# SOM_BOOT.net
KiCad netlist of a schematic drawn in Altium Designer
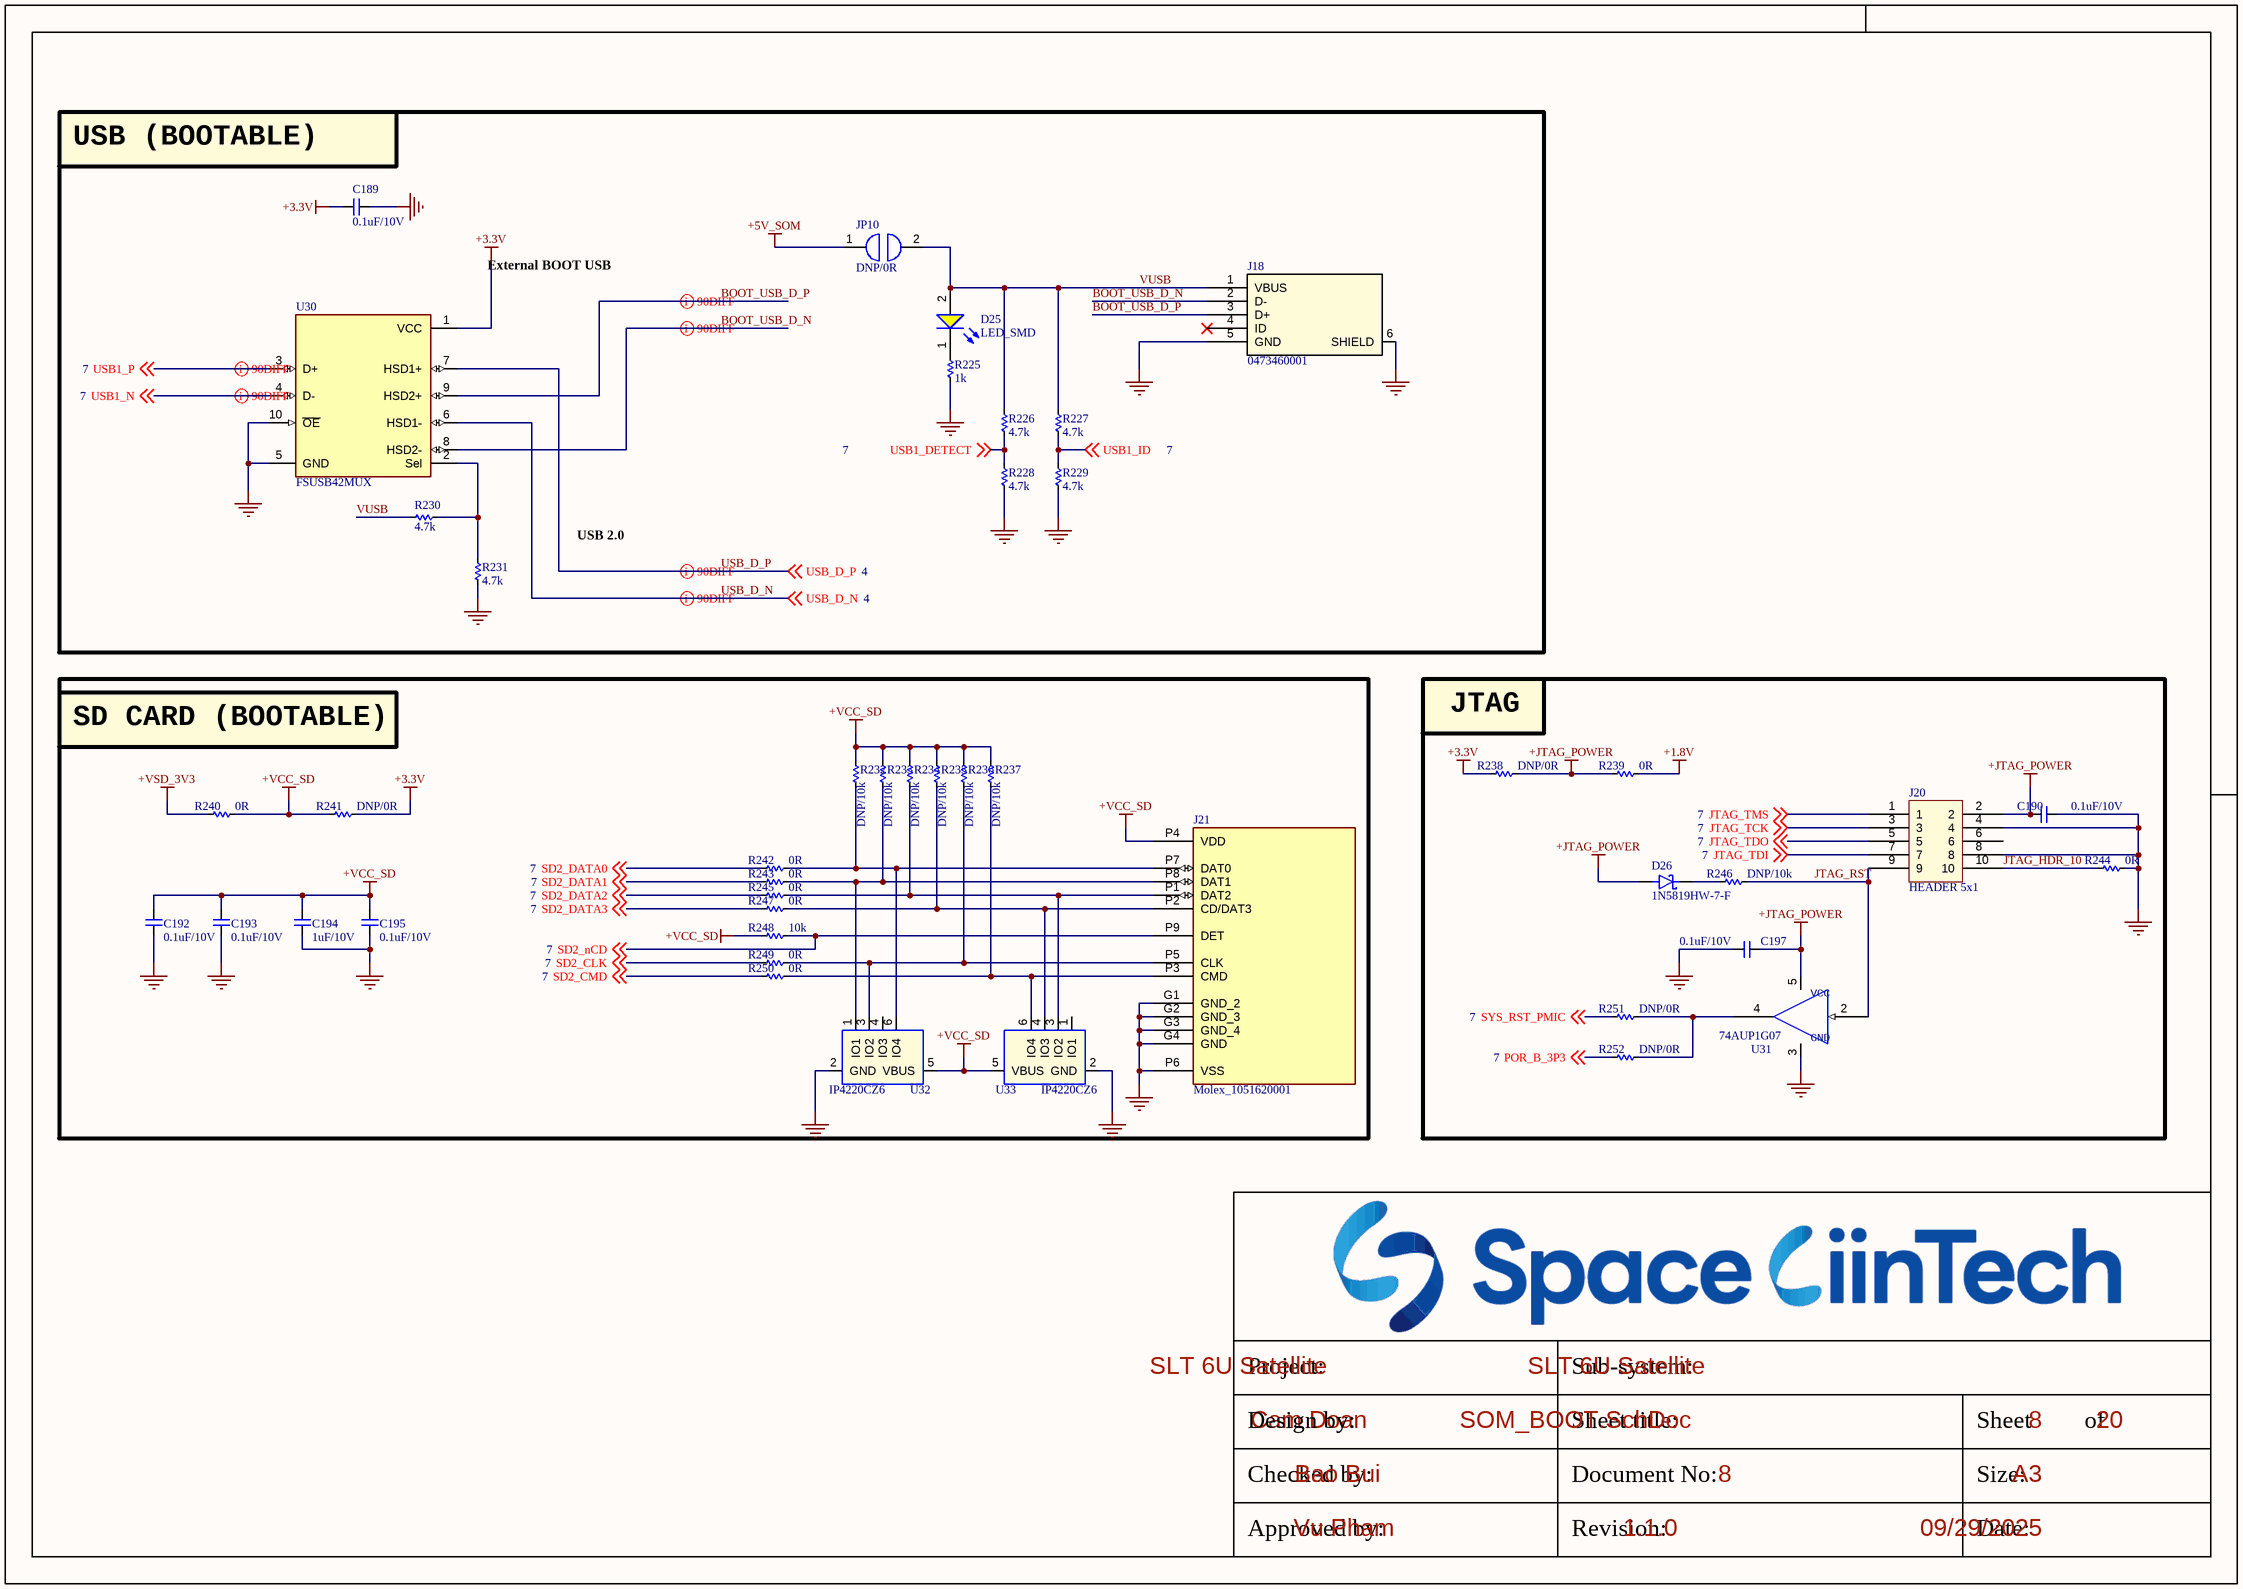
[diagram p0: SOM_BOOT.SchDoc]

(export (version "E")
  (design (tool "Eeschema 10.0.6"))
  (components
    (comp (ref "C189")
      (value "0.1uF/10V")
      (footprint "CAP_C_1005X60")
      (description "CAP CHIP")
      (libsource (lib "LABLIB") (part "_CAP_C_2"))
    )
    (comp (ref "C190")
      (value "0.1uF/10V")
      (footprint "CAP_C_1005X60")
      (description "CAP CHIP")
      (libsource (lib "LABLIB") (part "_CAP_C_2"))
    )
    (comp (ref "C192")
      (value "0.1uF/10V")
      (footprint "CAP_C_1005X60")
      (description "CAP CHIP")
      (libsource (lib "LABLIB") (part "_CAP_C_2"))
    )
    (comp (ref "C193")
      (value "0.1uF/10V")
      (footprint "CAP_C_1005X60")
      (description "CAP CHIP")
      (libsource (lib "LABLIB") (part "_CAP_C_2"))
    )
    (comp (ref "C194")
      (value "1uF/10V")
      (footprint "CAP_C_1005X60")
      (description "CAP CHIP")
      (libsource (lib "LABLIB") (part "_CAP_C_2"))
    )
    (comp (ref "C195")
      (value "0.1uF/10V")
      (footprint "CAP_C_1005X60")
      (description "CAP CHIP")
      (libsource (lib "LABLIB") (part "_CAP_C_2"))
    )
    (comp (ref "C197")
      (value "0.1uF/10V")
      (footprint "CAP_C_1005X60")
      (description "CAP CHIP")
      (libsource (lib "LABLIB") (part "_CAP_C_2"))
    )
    (comp (ref "D25") (value "LED_SMD") (footprint "LED_0603") (libsource (lib "LABLIB") (part "LED_SMD")))
    (comp (ref "D26")
      (value "1N5819HW-7-F")
      (footprint "SOD3717X145N")
      (description "DIODE SCHOTTKY 40V 1A SOD123")
      (libsource (lib "LABLIB") (part "DIODE SCHOTTKY"))
    )
    (comp (ref "J18")
      (value "0473460001")
      (footprint "47346-0001_MOL")
      (description "No Description Available")
      (libsource (lib "obc_ver2") (part "USB_micro"))
    )
    (comp (ref "J20")
      (value "HEADER 5x1")
      (footprint "CONN_54202-T0805ALF")
      (libsource (lib "LABLIB") (part "Header 5x2_Z"))
    )
    (comp (ref "J21")
      (value "Molex_1051620001")
      (footprint "Molex_1051620001")
      (description "9 (8 + 1) Position Card Connector Secure Digital - microSDâ„¢ Surface Mount, Right Angle Gold")
      (fields (field (name "MF") "Molex") (field (name "MP") "1051620001"))
      (libsource (lib "new_component") (part "Molex_1051620001"))
    )
    (comp (ref "JP10")
      (value "DNP/0R")
      (footprint "RES_C_1608X60")
      (libsource (lib "EXP_V1") (part "JUMPER"))
    )
    (comp (ref "R225")
      (value "1k")
      (footprint "RES_C_1005X40")
      (description "RES")
      (libsource (lib "LABLIB") (part "_RES_B_2"))
    )
    (comp (ref "R226")
      (value "4.7k")
      (footprint "RES_C_1005X40")
      (description "RES")
      (libsource (lib "LABLIB") (part "_RES_B_2"))
    )
    (comp (ref "R227")
      (value "4.7k")
      (footprint "RES_C_1005X40")
      (description "RES")
      (libsource (lib "LABLIB") (part "_RES_B_2"))
    )
    (comp (ref "R228")
      (value "4.7k")
      (footprint "RES_C_1005X40")
      (description "RES")
      (libsource (lib "LABLIB") (part "_RES_B_2"))
    )
    (comp (ref "R229")
      (value "4.7k")
      (footprint "RES_C_1005X40")
      (description "RES")
      (libsource (lib "LABLIB") (part "_RES_B_2"))
    )
    (comp (ref "R230")
      (value "4.7k")
      (footprint "RES_C_1005X40")
      (description "RES")
      (libsource (lib "LABLIB") (part "_RES_B_2"))
    )
    (comp (ref "R231")
      (value "4.7k")
      (footprint "RES_C_1005X40")
      (description "RES")
      (libsource (lib "LABLIB") (part "_RES_B_2"))
    )
    (comp (ref "R232")
      (value "DNP/10k")
      (footprint "RES_C_1005X40")
      (description "RES")
      (libsource (lib "LABLIB") (part "_RES_B_2"))
    )
    (comp (ref "R233")
      (value "DNP/10k")
      (footprint "RES_C_1005X40")
      (description "RES")
      (libsource (lib "LABLIB") (part "_RES_B_2"))
    )
    (comp (ref "R234")
      (value "DNP/10k")
      (footprint "RES_C_1005X40")
      (description "RES")
      (libsource (lib "LABLIB") (part "_RES_B_2"))
    )
    (comp (ref "R235")
      (value "DNP/10k")
      (footprint "RES_C_1005X40")
      (description "RES")
      (libsource (lib "LABLIB") (part "_RES_B_2"))
    )
    (comp (ref "R236")
      (value "DNP/10k")
      (footprint "RES_C_1005X40")
      (description "RES")
      (libsource (lib "LABLIB") (part "_RES_B_2"))
    )
    (comp (ref "R237")
      (value "DNP/10k")
      (footprint "RES_C_1005X40")
      (description "RES")
      (libsource (lib "LABLIB") (part "_RES_B_2"))
    )
    (comp (ref "R238")
      (value "DNP/0R")
      (footprint "RES_C_1005X40")
      (description "RES")
      (libsource (lib "LABLIB") (part "_RES_B_2"))
    )
    (comp (ref "R239")
      (value "0R")
      (footprint "RES_C_1005X40")
      (description "RES")
      (libsource (lib "LABLIB") (part "_RES_B_2"))
    )
    (comp (ref "R240")
      (value "0R")
      (footprint "RES_C_1005X40")
      (description "RES")
      (libsource (lib "LABLIB") (part "_RES_B_2"))
    )
    (comp (ref "R241")
      (value "DNP/0R")
      (footprint "RES_C_1005X40")
      (description "RES")
      (libsource (lib "LABLIB") (part "_RES_B_2"))
    )
    (comp (ref "R242")
      (value "0R")
      (footprint "RES_C_1005X40")
      (description "RES")
      (libsource (lib "LABLIB") (part "_RES_B_2"))
    )
    (comp (ref "R243")
      (value "0R")
      (footprint "RES_C_1005X40")
      (description "RES")
      (libsource (lib "LABLIB") (part "_RES_B_2"))
    )
    (comp (ref "R244")
      (value "0R")
      (footprint "RES_C_1005X40")
      (description "RES")
      (libsource (lib "LABLIB") (part "_RES_B_2"))
    )
    (comp (ref "R245")
      (value "0R")
      (footprint "RES_C_1005X40")
      (description "RES")
      (libsource (lib "LABLIB") (part "_RES_B_2"))
    )
    (comp (ref "R246")
      (value "DNP/10k")
      (footprint "RES_C_1005X40")
      (description "RES")
      (libsource (lib "LABLIB") (part "_RES_B_2"))
    )
    (comp (ref "R247")
      (value "0R")
      (footprint "RES_C_1005X40")
      (description "RES")
      (libsource (lib "LABLIB") (part "_RES_B_2"))
    )
    (comp (ref "R248")
      (value "10k")
      (footprint "RES_C_1005X40")
      (description "RES")
      (libsource (lib "LABLIB") (part "_RES_B_2"))
    )
    (comp (ref "R249")
      (value "0R")
      (footprint "RES_C_1005X40")
      (description "RES")
      (libsource (lib "LABLIB") (part "_RES_B_2"))
    )
    (comp (ref "R250")
      (value "0R")
      (footprint "RES_C_1005X40")
      (description "RES")
      (libsource (lib "LABLIB") (part "_RES_B_2"))
    )
    (comp (ref "R251")
      (value "DNP/0R")
      (footprint "RES_C_1005X40")
      (description "RES")
      (libsource (lib "LABLIB") (part "_RES_B_2"))
    )
    (comp (ref "R252")
      (value "DNP/0R")
      (footprint "RES_C_1005X40")
      (description "RES")
      (libsource (lib "LABLIB") (part "_RES_B_2"))
    )
    (comp (ref "U30")
      (value "FSUSB42MUX")
      (footprint "FP-846AP-MFG")
      (description "IC USB SWITCH DPDT 10MSOP")
      (fields (field (name "VOLTAGE") "4.3V"))
      (libsource (lib "Altium Content Vault") (part "e0bd5e1b4e0e4edc77f3356c64bf8f9"))
    )
    (comp (ref "U31")
      (value "74AUP1G07")
      (footprint "SOT-23-5_DIO")
      (libsource (lib "*") (part "74AUP1G07 , buffer ,LV"))
    )
    (comp (ref "U32")
      (value "IP4220CZ6")
      (footprint "SOT95P280X145-6N")
      (libsource (lib "") (part "IP4220CZ6_0_1"))
    )
    (comp (ref "U33")
      (value "IP4220CZ6")
      (footprint "SOT95P280X145-6N")
      (libsource (lib "*") (part "IP4220CZ6_0"))
    )
  )
  (nets
    (net (code "1") (name "+1.8V") (class "Default")
      (node (ref "R239") (pin "1") (pinfunction "1_1") (pintype "passive"))
    )
    (net (code "2") (name "+3.3V") (class "Default")
      (node (ref "C189") (pin "2") (pinfunction "2_2") (pintype "passive"))
      (node (ref "R238") (pin "2") (pinfunction "2_2") (pintype "passive"))
      (node (ref "R241") (pin "2") (pinfunction "2_2") (pintype "passive"))
      (node (ref "U30") (pin "1") (pinfunction "VCC_1") (pintype "power_in"))
    )
    (net (code "3") (name "+5V_SOM") (class "Default")
      (node (ref "JP10") (pin "1") (pinfunction "1_1") (pintype "passive"))
    )
    (net (code "4") (name "+JTAG_POWER") (class "Default")
      (node (ref "C190") (pin "2") (pinfunction "2_2") (pintype "passive"))
      (node (ref "C197") (pin "1") (pinfunction "1_1") (pintype "passive"))
      (node (ref "D26") (pin "2") (pinfunction "A_2") (pintype "passive"))
      (node (ref "J20") (pin "2") (pinfunction "2_2") (pintype "passive"))
      (node (ref "R238") (pin "1") (pinfunction "1_1") (pintype "passive"))
      (node (ref "R239") (pin "2") (pinfunction "2_2") (pintype "passive"))
      (node (ref "U31") (pin "5") (pinfunction "VCC_5") (pintype "power_in"))
    )
    (net (code "5") (name "+VCC_SD") (class "Default")
      (node (ref "C192") (pin "2") (pinfunction "2_2") (pintype "passive"))
      (node (ref "C193") (pin "2") (pinfunction "2_2") (pintype "passive"))
      (node (ref "C194") (pin "2") (pinfunction "2_2") (pintype "passive"))
      (node (ref "C195") (pin "2") (pinfunction "2_2") (pintype "passive"))
      (node (ref "J21") (pin "P4") (pinfunction "VDD_P4") (pintype "power_in"))
      (node (ref "R232") (pin "2") (pinfunction "2_2") (pintype "passive"))
      (node (ref "R233") (pin "2") (pinfunction "2_2") (pintype "passive"))
      (node (ref "R234") (pin "2") (pinfunction "2_2") (pintype "passive"))
      (node (ref "R235") (pin "2") (pinfunction "2_2") (pintype "passive"))
      (node (ref "R236") (pin "2") (pinfunction "2_2") (pintype "passive"))
      (node (ref "R237") (pin "2") (pinfunction "2_2") (pintype "passive"))
      (node (ref "R240") (pin "2") (pinfunction "2_2") (pintype "passive"))
      (node (ref "R241") (pin "1") (pinfunction "1_1") (pintype "passive"))
      (node (ref "R248") (pin "1") (pinfunction "1_1") (pintype "passive"))
      (node (ref "U32") (pin "5") (pinfunction "VBUS_5") (pintype "passive"))
      (node (ref "U33") (pin "5") (pinfunction "VBUS_5") (pintype "passive"))
    )
    (net (code "6") (name "+VSD_3V3") (class "Default")
      (node (ref "R240") (pin "1") (pinfunction "1_1") (pintype "passive"))
    )
    (net (code "7") (name "/BOOT_USB_D_N") (class "Default")
      (node (ref "J18") (pin "2") (pinfunction "D-_2") (pintype "passive"))
      (node (ref "U30") (pin "8") (pinfunction "HSD2-_8") (pintype "bidirectional"))
    )
    (net (code "8") (name "/BOOT_USB_D_P") (class "Default")
      (node (ref "J18") (pin "3") (pinfunction "D+_3") (pintype "passive"))
      (node (ref "U30") (pin "9") (pinfunction "HSD2+_9") (pintype "bidirectional"))
    )
    (net (code "9") (name "/JTAG_HDR_10") (class "Default")
      (node (ref "J20") (pin "10") (pinfunction "10_10") (pintype "passive"))
      (node (ref "R244") (pin "2") (pinfunction "2_2") (pintype "passive"))
    )
    (net (code "10") (name "/JTAG_RST") (class "Default")
      (node (ref "J20") (pin "9") (pinfunction "9_9") (pintype "passive"))
      (node (ref "R246") (pin "1") (pinfunction "1_1") (pintype "passive"))
      (node (ref "U31") (pin "2") (pinfunction "IN_2") (pintype "input"))
    )
    (net (code "11") (name "/VUSB") (class "Default")
      (node (ref "D25") (pin "2") (pinfunction "A_2") (pintype "passive"))
      (node (ref "J18") (pin "1") (pinfunction "VBUS_1") (pintype "passive"))
      (node (ref "JP10") (pin "2") (pinfunction "2_2") (pintype "passive"))
      (node (ref "R226") (pin "2") (pinfunction "2_2") (pintype "passive"))
      (node (ref "R227") (pin "2") (pinfunction "2_2") (pintype "passive"))
      (node (ref "R230") (pin "1") (pinfunction "1_1") (pintype "passive"))
    )
    (net (code "12") (name "GND") (class "Default")
      (node (ref "C189") (pin "1") (pinfunction "1_1") (pintype "passive"))
      (node (ref "C190") (pin "1") (pinfunction "1_1") (pintype "passive"))
      (node (ref "C192") (pin "1") (pinfunction "1_1") (pintype "passive"))
      (node (ref "C193") (pin "1") (pinfunction "1_1") (pintype "passive"))
      (node (ref "C194") (pin "1") (pinfunction "1_1") (pintype "passive"))
      (node (ref "C195") (pin "1") (pinfunction "1_1") (pintype "passive"))
      (node (ref "C197") (pin "2") (pinfunction "2_2") (pintype "passive"))
      (node (ref "J18") (pin "5") (pinfunction "GND_5") (pintype "power_in"))
      (node (ref "J18") (pin "6") (pinfunction "SHIELD_6") (pintype "passive"))
      (node (ref "J20") (pin "4") (pinfunction "4_4") (pintype "passive"))
      (node (ref "J20") (pin "8") (pinfunction "8_8") (pintype "passive"))
      (node (ref "J21") (pin "G1") (pinfunction "GND_2_G1") (pintype "passive"))
      (node (ref "J21") (pin "G2") (pinfunction "GND_3_G2") (pintype "passive"))
      (node (ref "J21") (pin "G3") (pinfunction "GND_4_G3") (pintype "passive"))
      (node (ref "J21") (pin "G4") (pinfunction "GND_G4") (pintype "passive"))
      (node (ref "J21") (pin "P6") (pinfunction "VSS_P6") (pintype "passive"))
      (node (ref "R225") (pin "1") (pinfunction "1_1") (pintype "passive"))
      (node (ref "R228") (pin "1") (pinfunction "1_1") (pintype "passive"))
      (node (ref "R229") (pin "1") (pinfunction "1_1") (pintype "passive"))
      (node (ref "R231") (pin "1") (pinfunction "1_1") (pintype "passive"))
      (node (ref "R244") (pin "1") (pinfunction "1_1") (pintype "passive"))
      (node (ref "U30") (pin "10") (pinfunction "~{OE}_10") (pintype "input"))
      (node (ref "U30") (pin "5") (pinfunction "GND_5") (pintype "power_in"))
      (node (ref "U31") (pin "3") (pinfunction "GND_3") (pintype "power_in"))
      (node (ref "U32") (pin "2") (pinfunction "GND_2") (pintype "passive"))
      (node (ref "U33") (pin "2") (pinfunction "GND_2") (pintype "passive"))
    )
    (net (code "13") (name "JTAG_TCK") (class "Default")
      (node (ref "J20") (pin "3") (pinfunction "3_3") (pintype "passive"))
    )
    (net (code "14") (name "JTAG_TDI") (class "Default")
      (node (ref "J20") (pin "7") (pinfunction "7_7") (pintype "passive"))
    )
    (net (code "15") (name "JTAG_TDO") (class "Default")
      (node (ref "J20") (pin "5") (pinfunction "5_5") (pintype "passive"))
    )
    (net (code "16") (name "JTAG_TMS") (class "Default")
      (node (ref "J20") (pin "1") (pinfunction "1_1") (pintype "passive"))
    )
    (net (code "17") (name "Net-(D25-K)") (class "Default")
      (node (ref "D25") (pin "1") (pinfunction "K_1") (pintype "passive"))
      (node (ref "R225") (pin "2") (pinfunction "2_2") (pintype "passive"))
    )
    (net (code "18") (name "Net-(D26-K)") (class "Default")
      (node (ref "D26") (pin "1") (pinfunction "K_1") (pintype "passive"))
      (node (ref "R246") (pin "2") (pinfunction "2_2") (pintype "passive"))
    )
    (net (code "19") (name "Net-(J21-CD{slash}DAT3)") (class "Default")
      (node (ref "J21") (pin "P2") (pinfunction "CD/DAT3_P2") (pintype "passive"))
      (node (ref "R235") (pin "1") (pinfunction "1_1") (pintype "passive"))
      (node (ref "R247") (pin "2") (pinfunction "2_2") (pintype "passive"))
      (node (ref "U33") (pin "4") (pinfunction "IO3_4") (pintype "passive"))
    )
    (net (code "20") (name "Net-(J21-CLK)") (class "Default")
      (node (ref "J21") (pin "P5") (pinfunction "CLK_P5") (pintype "passive"))
      (node (ref "R236") (pin "1") (pinfunction "1_1") (pintype "passive"))
      (node (ref "R249") (pin "2") (pinfunction "2_2") (pintype "passive"))
      (node (ref "U32") (pin "3") (pinfunction "IO2_3") (pintype "passive"))
    )
    (net (code "21") (name "Net-(J21-CMD)") (class "Default")
      (node (ref "J21") (pin "P3") (pinfunction "CMD_P3") (pintype "passive"))
      (node (ref "R237") (pin "1") (pinfunction "1_1") (pintype "passive"))
      (node (ref "R250") (pin "2") (pinfunction "2_2") (pintype "passive"))
      (node (ref "U33") (pin "6") (pinfunction "IO4_6") (pintype "passive"))
    )
    (net (code "22") (name "Net-(J21-DAT0)") (class "Default")
      (node (ref "J21") (pin "P7") (pinfunction "DAT0_P7") (pintype "bidirectional"))
      (node (ref "R232") (pin "1") (pinfunction "1_1") (pintype "passive"))
      (node (ref "R242") (pin "2") (pinfunction "2_2") (pintype "passive"))
      (node (ref "U32") (pin "6") (pinfunction "IO4_6") (pintype "passive"))
    )
    (net (code "23") (name "Net-(J21-DAT1)") (class "Default")
      (node (ref "J21") (pin "P8") (pinfunction "DAT1_P8") (pintype "bidirectional"))
      (node (ref "R233") (pin "1") (pinfunction "1_1") (pintype "passive"))
      (node (ref "R243") (pin "2") (pinfunction "2_2") (pintype "passive"))
      (node (ref "U32") (pin "1") (pinfunction "IO1_1") (pintype "passive"))
    )
    (net (code "24") (name "Net-(J21-DAT2)") (class "Default")
      (node (ref "J21") (pin "P1") (pinfunction "DAT2_P1") (pintype "bidirectional"))
      (node (ref "R234") (pin "1") (pinfunction "1_1") (pintype "passive"))
      (node (ref "R245") (pin "2") (pinfunction "2_2") (pintype "passive"))
      (node (ref "U33") (pin "3") (pinfunction "IO2_3") (pintype "passive"))
    )
    (net (code "25") (name "Net-(U30-Sel)") (class "Default")
      (node (ref "R230") (pin "2") (pinfunction "2_2") (pintype "passive"))
      (node (ref "R231") (pin "2") (pinfunction "2_2") (pintype "passive"))
      (node (ref "U30") (pin "2") (pinfunction "Sel_2") (pintype "passive"))
    )
    (net (code "26") (name "Net-(U31-OUT)") (class "Default")
      (node (ref "R251") (pin "1") (pinfunction "1_1") (pintype "passive"))
      (node (ref "R252") (pin "1") (pinfunction "1_1") (pintype "passive"))
      (node (ref "U31") (pin "4") (pinfunction "OUT_4") (pintype "open_collector"))
    )
    (net (code "27") (name "POR_B_3P3") (class "Default")
      (node (ref "R252") (pin "2") (pinfunction "2_2") (pintype "passive"))
    )
    (net (code "28") (name "SD2_CLK") (class "Default")
      (node (ref "R249") (pin "1") (pinfunction "1_1") (pintype "passive"))
    )
    (net (code "29") (name "SD2_CMD") (class "Default")
      (node (ref "R250") (pin "1") (pinfunction "1_1") (pintype "passive"))
    )
    (net (code "30") (name "SD2_DATA0") (class "Default")
      (node (ref "R242") (pin "1") (pinfunction "1_1") (pintype "passive"))
    )
    (net (code "31") (name "SD2_DATA1") (class "Default")
      (node (ref "R243") (pin "1") (pinfunction "1_1") (pintype "passive"))
    )
    (net (code "32") (name "SD2_DATA2") (class "Default")
      (node (ref "R245") (pin "1") (pinfunction "1_1") (pintype "passive"))
    )
    (net (code "33") (name "SD2_DATA3") (class "Default")
      (node (ref "R247") (pin "1") (pinfunction "1_1") (pintype "passive"))
    )
    (net (code "34") (name "SD2_nCD") (class "Default")
      (node (ref "J21") (pin "P9") (pinfunction "DET_P9") (pintype "passive"))
      (node (ref "R248") (pin "2") (pinfunction "2_2") (pintype "passive"))
    )
    (net (code "35") (name "SYS_RST_PMIC") (class "Default")
      (node (ref "R251") (pin "2") (pinfunction "2_2") (pintype "passive"))
    )
    (net (code "36") (name "USB1_DETECT") (class "Default")
      (node (ref "R226") (pin "1") (pinfunction "1_1") (pintype "passive"))
      (node (ref "R228") (pin "2") (pinfunction "2_2") (pintype "passive"))
    )
    (net (code "37") (name "USB1_ID") (class "Default")
      (node (ref "R227") (pin "1") (pinfunction "1_1") (pintype "passive"))
      (node (ref "R229") (pin "2") (pinfunction "2_2") (pintype "passive"))
    )
    (net (code "38") (name "USB1_N") (class "Default")
      (node (ref "U30") (pin "4") (pinfunction "D-_4") (pintype "bidirectional"))
    )
    (net (code "39") (name "USB1_P") (class "Default")
      (node (ref "U30") (pin "3") (pinfunction "D+_3") (pintype "bidirectional"))
    )
    (net (code "40") (name "USB_D_N") (class "Default")
      (node (ref "U30") (pin "6") (pinfunction "HSD1-_6") (pintype "bidirectional"))
    )
    (net (code "41") (name "USB_D_P") (class "Default")
      (node (ref "U30") (pin "7") (pinfunction "HSD1+_7") (pintype "bidirectional"))
    )
    (net (code "42") (name "unconnected-(J18-ID-Pad4)") (class "Default")
      (node (ref "J18") (pin "4") (pinfunction "ID_4") (pintype "passive+no_connect"))
    )
    (net (code "43") (name "unconnected-(J20-Pad6)") (class "Default")
      (node (ref "J20") (pin "6") (pinfunction "6_6") (pintype "passive"))
    )
    (net (code "44") (name "unconnected-(U32-IO3-Pad4)") (class "Default")
      (node (ref "U32") (pin "4") (pinfunction "IO3_4") (pintype "passive"))
    )
    (net (code "45") (name "unconnected-(U33-IO1-Pad1)") (class "Default")
      (node (ref "U33") (pin "1") (pinfunction "IO1_1") (pintype "passive"))
    )
  )
)
